# RadarControl_V1_00.net
KiCad netlist of a schematic drawn in Altium Designer
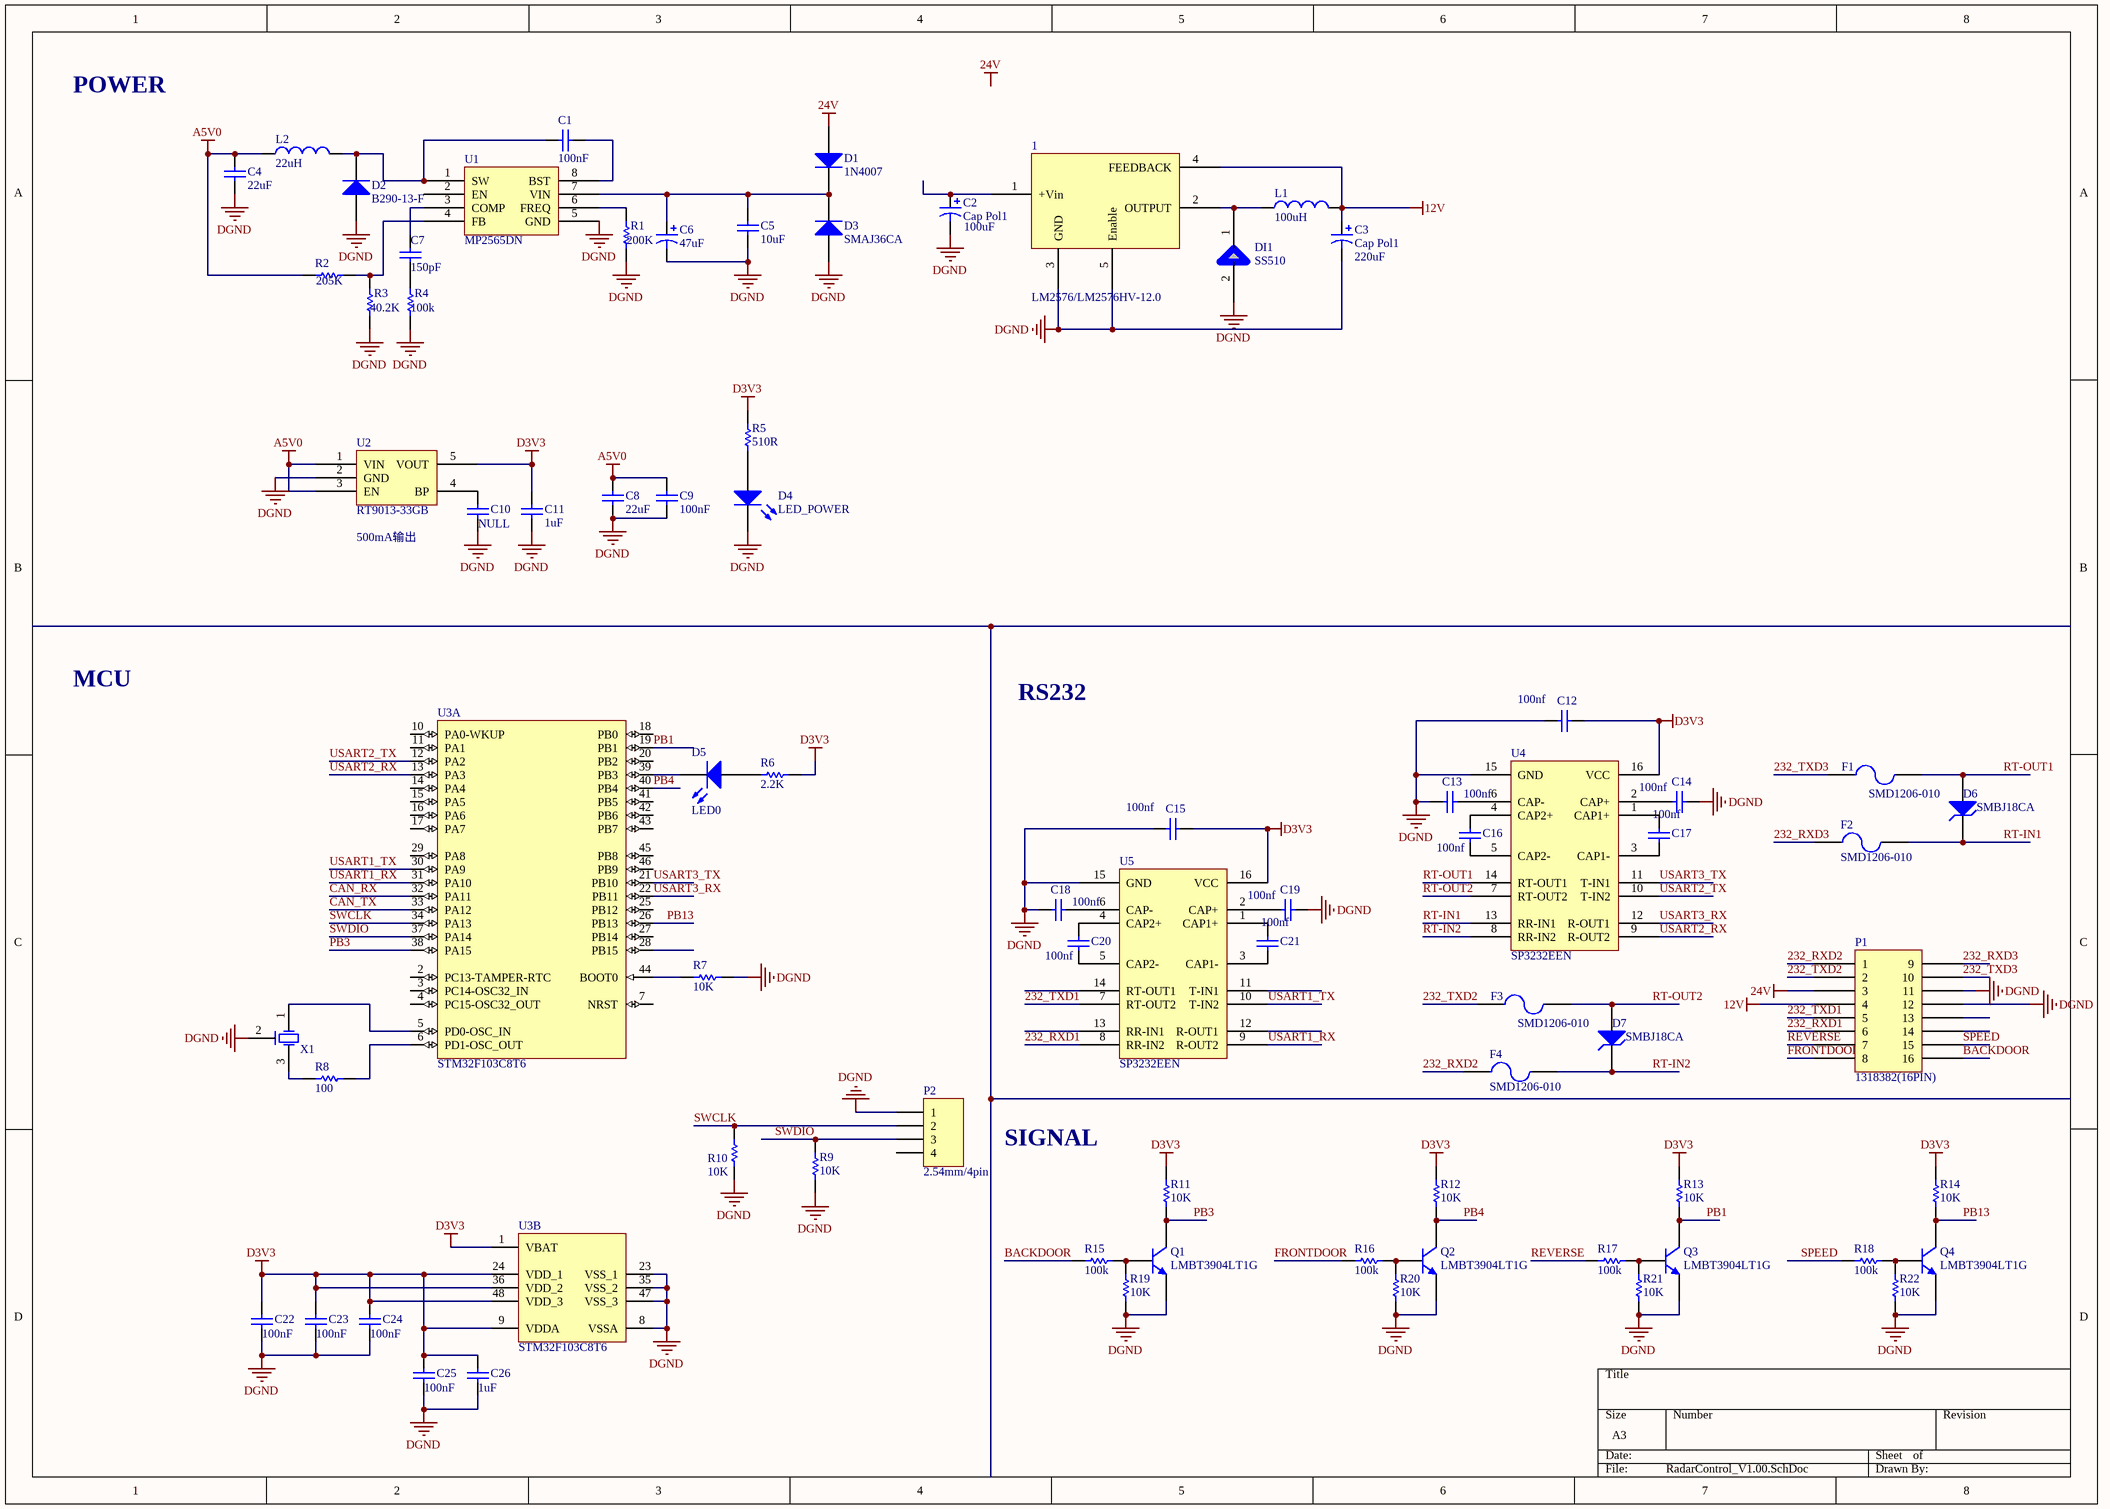
[diagram p0: RadarControl_V1.00.SchDoc]

(export (version "E")
  (design (tool "Eeschema 10.0.6"))
  (components
    (comp (ref "1")
      (value "LM2576/LM2576HV-12.0")
      (footprint "LM25761")
      (libsource (lib "Schlib1") (part "LM2576-FIX"))
    )
    (comp (ref "C1")
      (value "100nF")
      (footprint "0603")
      (description "Capacitor")
      (fields (field (name "PUBLISHER") "Altium Limited"))
      (libsource (lib "Miscellaneous Devices") (part "Cap"))
    )
    (comp (ref "C2")
      (value "Cap Pol1")
      (footprint "Cap-100uF-220uF")
      (description "Polarized Capacitor (Radial)")
      (fields (field (name "ALTIUM_VALUE") "100uF") (field (name "PUBLISHER") "Altium Limited"))
      (libsource (lib "Miscellaneous Devices") (part "Cap Pol1"))
    )
    (comp (ref "C3")
      (value "Cap Pol1")
      (footprint "Cap-100uF-220uF")
      (description "Polarized Capacitor (Radial)")
      (fields (field (name "ALTIUM_VALUE") "220uF") (field (name "PUBLISHER") "Altium Limited"))
      (libsource (lib "Miscellaneous Devices") (part "Cap Pol1"))
    )
    (comp (ref "C4")
      (value "22uF")
      (footprint "0805")
      (description "Capacitor,50V")
      (fields (field (name "PUBLISHER") "Altium Limited"))
      (libsource (lib "Miscellaneous Devices") (part "Cap"))
    )
    (comp (ref "C5")
      (value "10uF")
      (footprint "0805")
      (description "Capacitor,50V")
      (fields (field (name "PUBLISHER") "Altium Limited"))
      (libsource (lib "Miscellaneous Devices") (part "Cap"))
    )
    (comp (ref "C6")
      (value "47uF")
      (footprint "cap_pol_8*10.2")
      (description "Polarized Capacitor (Radial)")
      (fields (field (name "PUBLISHER") "Altium Limited"))
      (libsource (lib "Miscellaneous Devices") (part "Cap Pol1"))
    )
    (comp (ref "C7")
      (value "150pF")
      (footprint "0603")
      (description "Capacitor")
      (fields (field (name "PUBLISHER") "Altium Limited"))
      (libsource (lib "Miscellaneous Devices") (part "Cap"))
    )
    (comp (ref "C8")
      (value "22uF")
      (footprint "1206")
      (description "Capacitor")
      (fields (field (name "PUBLISHER") "Altium Limited"))
      (libsource (lib "Miscellaneous Devices") (part "Cap"))
    )
    (comp (ref "C9")
      (value "100nF")
      (footprint "0402")
      (description "Capacitor 5V")
      (fields (field (name "PUBLISHER") "Altium Limited"))
      (libsource (lib "Miscellaneous Devices") (part "Cap"))
    )
    (comp (ref "C10")
      (value "NULL")
      (footprint "0402")
      (description "Capacitor")
      (fields (field (name "PUBLISHER") "Altium Limited"))
      (libsource (lib "Miscellaneous Devices") (part "Cap"))
    )
    (comp (ref "C11")
      (value "1uF")
      (footprint "0402")
      (description "Capacitor 3V3")
      (fields (field (name "PUBLISHER") "Altium Limited"))
      (libsource (lib "Miscellaneous Devices") (part "Cap"))
    )
    (comp (ref "C12")
      (value "100nf")
      (footprint "0402")
      (description "Capacitor")
      (fields (field (name "PUBLISHER") "Altium Limited"))
      (libsource (lib "Miscellaneous Devices") (part "Cap"))
    )
    (comp (ref "C13")
      (value "100nf")
      (footprint "0402")
      (description "Capacitor")
      (fields (field (name "PUBLISHER") "Altium Limited"))
      (libsource (lib "Miscellaneous Devices") (part "Cap"))
    )
    (comp (ref "C14")
      (value "100nf")
      (footprint "0402")
      (description "Capacitor")
      (fields (field (name "PUBLISHER") "Altium Limited"))
      (libsource (lib "Miscellaneous Devices") (part "Cap"))
    )
    (comp (ref "C15")
      (value "100nf")
      (footprint "0402")
      (description "Capacitor")
      (fields (field (name "PUBLISHER") "Altium Limited"))
      (libsource (lib "Miscellaneous Devices") (part "Cap"))
    )
    (comp (ref "C16")
      (value "100nf")
      (footprint "0402")
      (description "Capacitor")
      (fields (field (name "PUBLISHER") "Altium Limited"))
      (libsource (lib "Miscellaneous Devices") (part "Cap"))
    )
    (comp (ref "C17")
      (value "100nf")
      (footprint "0402")
      (description "Capacitor")
      (fields (field (name "PUBLISHER") "Altium Limited"))
      (libsource (lib "Miscellaneous Devices") (part "Cap"))
    )
    (comp (ref "C18")
      (value "100nf")
      (footprint "0402")
      (description "Capacitor")
      (fields (field (name "PUBLISHER") "Altium Limited"))
      (libsource (lib "Miscellaneous Devices") (part "Cap"))
    )
    (comp (ref "C19")
      (value "100nf")
      (footprint "0402")
      (description "Capacitor")
      (fields (field (name "PUBLISHER") "Altium Limited"))
      (libsource (lib "Miscellaneous Devices") (part "Cap"))
    )
    (comp (ref "C20")
      (value "100nf")
      (footprint "0402")
      (description "Capacitor")
      (fields (field (name "PUBLISHER") "Altium Limited"))
      (libsource (lib "Miscellaneous Devices") (part "Cap"))
    )
    (comp (ref "C21")
      (value "100nf")
      (footprint "0402")
      (description "Capacitor")
      (fields (field (name "PUBLISHER") "Altium Limited"))
      (libsource (lib "Miscellaneous Devices") (part "Cap"))
    )
    (comp (ref "C22")
      (value "100nF")
      (footprint "0603")
      (description "Capacitor")
      (fields (field (name "PUBLISHER") "Altium Limited"))
      (libsource (lib "Miscellaneous Devices") (part "Cap"))
    )
    (comp (ref "C23")
      (value "100nF")
      (footprint "0402")
      (description "Capacitor")
      (fields (field (name "PUBLISHER") "Altium Limited"))
      (libsource (lib "Miscellaneous Devices") (part "Cap"))
    )
    (comp (ref "C24")
      (value "100nF")
      (footprint "0402")
      (description "Capacitor")
      (fields (field (name "PUBLISHER") "Altium Limited"))
      (libsource (lib "Miscellaneous Devices") (part "Cap"))
    )
    (comp (ref "C25")
      (value "100nF")
      (footprint "0402")
      (description "Capacitor")
      (fields (field (name "PUBLISHER") "Altium Limited"))
      (libsource (lib "Miscellaneous Devices") (part "Cap"))
    )
    (comp (ref "C26")
      (value "1uF")
      (footprint "0402")
      (description "Capacitor")
      (fields (field (name "PUBLISHER") "Altium Limited"))
      (libsource (lib "Miscellaneous Devices") (part "Cap"))
    )
    (comp (ref "D1")
      (value "1N4007")
      (footprint "B290")
      (description "1 Amp General Purpose Rectifier")
      (fields (field (name "PUBLISHER") "Altium Limited"))
      (libsource (lib "Miscellaneous Devices") (part "Diode 1N4007"))
    )
    (comp (ref "D2")
      (value "B290-13-F")
      (footprint "B290")
      (description "Default Diode")
      (fields (field (name "PUBLISHER") "Altium Limited"))
      (libsource (lib "Miscellaneous Devices") (part "Diode"))
    )
    (comp (ref "D3")
      (value "SMAJ36CA")
      (footprint "B290")
      (description "1 Amp General Purpose Rectifier")
      (fields (field (name "PUBLISHER") "Altium Limited"))
      (libsource (lib "Miscellaneous Devices") (part "Diode 1N4007"))
    )
    (comp (ref "D4")
      (value "LED_POWER")
      (footprint "0805-LED")
      (description "Typical INFRARED GaAs LED")
      (fields (field (name "PUBLISHER") "Altium Limited"))
      (libsource (lib "Miscellaneous Devices") (part "LED0"))
    )
    (comp (ref "D5")
      (value "LED0")
      (footprint "0805-LED")
      (description "green LED")
      (fields (field (name "PUBLISHER") "Altium Limited"))
      (libsource (lib "Miscellaneous Devices") (part "LED0"))
    )
    (comp (ref "D6")
      (value "SMBJ18CA")
      (footprint "SMB")
      (description "Zener Diode")
      (fields (field (name "PUBLISHER") "Altium Limited"))
      (libsource (lib "Miscellaneous Devices") (part "D Zener"))
    )
    (comp (ref "D7")
      (value "SMBJ18CA")
      (footprint "SMB")
      (description "Zener Diode")
      (fields (field (name "PUBLISHER") "Altium Limited"))
      (libsource (lib "Miscellaneous Devices") (part "D Zener"))
    )
    (comp (ref "DI1") (value "SS510") (footprint "SS510") (libsource (lib "Schlib2") (part "SS510")))
    (comp (ref "F1")
      (value "SMD1206-010")
      (footprint "1206")
      (description "Fuse")
      (fields (field (name "PUBLISHER") "Altium Limited"))
      (libsource (lib "Miscellaneous Devices") (part "Fuse 2"))
    )
    (comp (ref "F2")
      (value "SMD1206-010")
      (footprint "1206")
      (description "Fuse")
      (fields (field (name "PUBLISHER") "Altium Limited"))
      (libsource (lib "Miscellaneous Devices") (part "Fuse 2"))
    )
    (comp (ref "F3")
      (value "SMD1206-010")
      (footprint "1206")
      (description "Fuse")
      (fields (field (name "PUBLISHER") "Altium Limited"))
      (libsource (lib "Miscellaneous Devices") (part "Fuse 2"))
    )
    (comp (ref "F4")
      (value "SMD1206-010")
      (footprint "1206")
      (description "Fuse")
      (fields (field (name "PUBLISHER") "Altium Limited"))
      (libsource (lib "Miscellaneous Devices") (part "Fuse 2"))
    )
    (comp (ref "L1")
      (value "100uH")
      (footprint "GDRH104R-1R0MT")
      (description "Inductor")
      (fields (field (name "PUBLISHER") "Altium Limited"))
      (libsource (lib "原理图库") (part "Inductor"))
    )
    (comp (ref "L2")
      (value "22uH")
      (footprint "10*10Inductor")
      (description "Inductor, 1A")
      (fields (field (name "PUBLISHER") "Altium Limited"))
      (libsource (lib "Miscellaneous Devices") (part "Inductor"))
    )
    (comp (ref "P1")
      (value "1318382(16PIN)")
      (footprint "16pin 1318382")
      (libsource (lib "16PIN") (part "16PIN"))
    )
    (comp (ref "P2")
      (value "2.54mm/4pin")
      (footprint "HDR1X4")
      (description "Header, 4-Pin")
      (fields (field (name "PUBLISHER") "Altium Limited"))
      (libsource (lib "Miscellaneous Connectors") (part "Header 4"))
    )
    (comp (ref "Q1")
      (value "LMBT3904LT1G")
      (footprint "LC-SOT-23(SOT-23-3)")
      (description "NPN General Purpose Amplifier")
      (fields (field (name "PUBLISHER") "Altium Limited"))
      (libsource (lib "Miscellaneous Devices") (part "2N3904"))
    )
    (comp (ref "Q2")
      (value "LMBT3904LT1G")
      (footprint "LC-SOT-23(SOT-23-3)")
      (description "NPN General Purpose Amplifier")
      (fields (field (name "PUBLISHER") "Altium Limited"))
      (libsource (lib "Miscellaneous Devices") (part "2N3904"))
    )
    (comp (ref "Q3")
      (value "LMBT3904LT1G")
      (footprint "LC-SOT-23(SOT-23-3)")
      (description "NPN General Purpose Amplifier")
      (fields (field (name "PUBLISHER") "Altium Limited"))
      (libsource (lib "Miscellaneous Devices") (part "2N3904"))
    )
    (comp (ref "Q4")
      (value "LMBT3904LT1G")
      (footprint "LC-SOT-23(SOT-23-3)")
      (description "NPN General Purpose Amplifier")
      (fields (field (name "PUBLISHER") "Altium Limited"))
      (libsource (lib "Miscellaneous Devices") (part "2N3904"))
    )
    (comp (ref "R1")
      (value "200K")
      (footprint "0402")
      (description "Resistor")
      (fields (field (name "PUBLISHER") "Altium Limited"))
      (libsource (lib "Miscellaneous Devices") (part "Res1"))
    )
    (comp (ref "R2")
      (value "205K")
      (footprint "0603")
      (description "Resistor")
      (fields (field (name "PUBLISHER") "Altium Limited"))
      (libsource (lib "Miscellaneous Devices") (part "Res1"))
    )
    (comp (ref "R3")
      (value "40.2K")
      (footprint "0603")
      (description "Resistor")
      (fields (field (name "PUBLISHER") "Altium Limited"))
      (libsource (lib "Miscellaneous Devices") (part "Res1"))
    )
    (comp (ref "R4")
      (value "100k")
      (footprint "0603")
      (description "Resistor")
      (fields (field (name "PUBLISHER") "Altium Limited"))
      (libsource (lib "Miscellaneous Devices") (part "Res1"))
    )
    (comp (ref "R5")
      (value "510R")
      (footprint "0603")
      (description "Resistor")
      (fields (field (name "PUBLISHER") "Altium Limited"))
      (libsource (lib "Miscellaneous Devices") (part "Res1"))
    )
    (comp (ref "R6")
      (value "2.2K")
      (footprint "0402")
      (description "Resistor")
      (fields (field (name "PUBLISHER") "Altium Limited"))
      (libsource (lib "Miscellaneous Devices") (part "Res1"))
    )
    (comp (ref "R7")
      (value "10K")
      (footprint "0402")
      (description "Resistor")
      (fields (field (name "PUBLISHER") "Altium Limited"))
      (libsource (lib "Miscellaneous Devices") (part "Res1"))
    )
    (comp (ref "R8")
      (value "100")
      (footprint "0603")
      (description "Resistor")
      (fields (field (name "PUBLISHER") "Altium Limited"))
      (libsource (lib "Miscellaneous Devices") (part "Res1"))
    )
    (comp (ref "R9")
      (value "10K")
      (footprint "0402")
      (description "Resistor")
      (fields (field (name "Comment") "1K") (field (name "PUBLISHER") "Altium Limited"))
      (libsource (lib "Miscellaneous Devices") (part "Res1"))
    )
    (comp (ref "R10")
      (value "10K")
      (footprint "0402")
      (description "Resistor")
      (fields (field (name "Comment") "1K") (field (name "PUBLISHER") "Altium Limited"))
      (libsource (lib "Miscellaneous Devices") (part "Res1"))
    )
    (comp (ref "R11")
      (value "10K")
      (footprint "0402")
      (description "Resistor")
      (fields (field (name "PUBLISHER") "Altium Limited"))
      (libsource (lib "Miscellaneous Devices") (part "Res1"))
    )
    (comp (ref "R12")
      (value "10K")
      (footprint "0402")
      (description "Resistor")
      (fields (field (name "PUBLISHER") "Altium Limited"))
      (libsource (lib "Miscellaneous Devices") (part "Res1"))
    )
    (comp (ref "R13")
      (value "10K")
      (footprint "0402")
      (description "Resistor")
      (fields (field (name "PUBLISHER") "Altium Limited"))
      (libsource (lib "Miscellaneous Devices") (part "Res1"))
    )
    (comp (ref "R14")
      (value "10K")
      (footprint "0402")
      (description "Resistor")
      (fields (field (name "PUBLISHER") "Altium Limited"))
      (libsource (lib "Miscellaneous Devices") (part "Res1"))
    )
    (comp (ref "R15")
      (value "100k")
      (footprint "0402")
      (description "Resistor")
      (fields (field (name "PUBLISHER") "Altium Limited"))
      (libsource (lib "Miscellaneous Devices") (part "Res1"))
    )
    (comp (ref "R16")
      (value "100k")
      (footprint "0402")
      (description "Resistor")
      (fields (field (name "PUBLISHER") "Altium Limited"))
      (libsource (lib "Miscellaneous Devices") (part "Res1"))
    )
    (comp (ref "R17")
      (value "100k")
      (footprint "0402")
      (description "Resistor")
      (fields (field (name "PUBLISHER") "Altium Limited"))
      (libsource (lib "Miscellaneous Devices") (part "Res1"))
    )
    (comp (ref "R18")
      (value "100k")
      (footprint "0402")
      (description "Resistor")
      (fields (field (name "PUBLISHER") "Altium Limited"))
      (libsource (lib "Miscellaneous Devices") (part "Res1"))
    )
    (comp (ref "R19")
      (value "10K")
      (footprint "0402")
      (description "Resistor")
      (fields (field (name "PUBLISHER") "Altium Limited"))
      (libsource (lib "Miscellaneous Devices") (part "Res1"))
    )
    (comp (ref "R20")
      (value "10K")
      (footprint "0402")
      (description "Resistor")
      (fields (field (name "PUBLISHER") "Altium Limited"))
      (libsource (lib "Miscellaneous Devices") (part "Res1"))
    )
    (comp (ref "R21")
      (value "10K")
      (footprint "0402")
      (description "Resistor")
      (fields (field (name "PUBLISHER") "Altium Limited"))
      (libsource (lib "Miscellaneous Devices") (part "Res1"))
    )
    (comp (ref "R22")
      (value "10K")
      (footprint "0402")
      (description "Resistor")
      (fields (field (name "PUBLISHER") "Altium Limited"))
      (libsource (lib "Miscellaneous Devices") (part "Res1"))
    )
    (comp (ref "U1")
      (value "MP2565DN")
      (footprint "so-8")
      (description "DCDC 4.5V~28V input 1.8V ~5V output low power")
      (libsource (lib "BinFeng_IC") (part "MP1584"))
    )
    (comp (ref "U2")
      (value "RT9013-33GB")
      (footprint "SOT-23-5")
      (libsource (lib "BinFeng_IC") (part "RT9193"))
    )
    (comp (ref "U3")
      (value "STM32F103C8T6")
      (footprint "STM-LQFP48_M")
      (libsource (lib "STMicroelectronics STM32 F1") (part "STM32F103C8T6"))
    )
    (comp (ref "U4") (value "SP3232EEN") (footprint "SO-16") (libsource (lib "changyong") (part "MAX202")))
    (comp (ref "U5") (value "SP3232EEN") (footprint "SO-16") (libsource (lib "changyong") (part "MAX202")))
    (comp (ref "X1") (value "8M smd") (footprint "8M") (libsource (lib "Schlib1") (part "8M smd")))
  )
  (nets
    (net (code "1") (name "/232_RXD1") (class "Default")
      (node (ref "P1") (pin "6") (pinfunction "6_6") (pintype "passive"))
      (node (ref "U5") (pin "8") (pinfunction "RR-IN2_8") (pintype "passive"))
    )
    (net (code "2") (name "/232_RXD2") (class "Default")
      (node (ref "F4") (pin "1") (pinfunction "1_1") (pintype "passive"))
      (node (ref "P1") (pin "1") (pinfunction "1_1") (pintype "passive"))
    )
    (net (code "3") (name "/232_RXD3") (class "Default")
      (node (ref "F2") (pin "1") (pinfunction "1_1") (pintype "passive"))
      (node (ref "P1") (pin "9") (pinfunction "9_9") (pintype "passive"))
    )
    (net (code "4") (name "/232_TXD1") (class "Default")
      (node (ref "P1") (pin "5") (pinfunction "5_5") (pintype "passive"))
      (node (ref "U5") (pin "7") (pinfunction "RT-OUT2_7") (pintype "passive"))
    )
    (net (code "5") (name "/232_TXD2") (class "Default")
      (node (ref "F3") (pin "1") (pinfunction "1_1") (pintype "passive"))
      (node (ref "P1") (pin "2") (pinfunction "2_2") (pintype "passive"))
    )
    (net (code "6") (name "/232_TXD3") (class "Default")
      (node (ref "F1") (pin "1") (pinfunction "1_1") (pintype "passive"))
      (node (ref "P1") (pin "10") (pinfunction "10_10") (pintype "passive"))
    )
    (net (code "7") (name "/BACKDOOR") (class "Default")
      (node (ref "P1") (pin "16") (pinfunction "16_16") (pintype "passive"))
      (node (ref "R15") (pin "2") (pinfunction "2_2") (pintype "passive"))
    )
    (net (code "8") (name "/CAN_RX") (class "Default")
      (node (ref "U3") (pin "32") (pinfunction "PA11_32") (pintype "bidirectional"))
    )
    (net (code "9") (name "/CAN_TX") (class "Default")
      (node (ref "U3") (pin "33") (pinfunction "PA12_33") (pintype "bidirectional"))
    )
    (net (code "10") (name "/FRONTDOOR") (class "Default")
      (node (ref "P1") (pin "8") (pinfunction "8_8") (pintype "passive"))
      (node (ref "R16") (pin "2") (pinfunction "2_2") (pintype "passive"))
    )
    (net (code "11") (name "/PB1") (class "Default")
      (node (ref "Q3") (pin "3") (pinfunction "C_3") (pintype "passive"))
      (node (ref "R13") (pin "1") (pinfunction "1_1") (pintype "passive"))
      (node (ref "U3") (pin "19") (pinfunction "PB1_19") (pintype "bidirectional"))
    )
    (net (code "12") (name "/PB3") (class "Default")
      (node (ref "Q1") (pin "3") (pinfunction "C_3") (pintype "passive"))
      (node (ref "R11") (pin "1") (pinfunction "1_1") (pintype "passive"))
      (node (ref "U3") (pin "38") (pinfunction "PA15_38") (pintype "bidirectional"))
    )
    (net (code "13") (name "/PB4") (class "Default")
      (node (ref "Q2") (pin "3") (pinfunction "C_3") (pintype "passive"))
      (node (ref "R12") (pin "1") (pinfunction "1_1") (pintype "passive"))
      (node (ref "U3") (pin "40") (pinfunction "PB4_40") (pintype "bidirectional"))
    )
    (net (code "14") (name "/PB13") (class "Default")
      (node (ref "Q4") (pin "3") (pinfunction "C_3") (pintype "passive"))
      (node (ref "R14") (pin "1") (pinfunction "1_1") (pintype "passive"))
      (node (ref "U3") (pin "26") (pinfunction "PB13_26") (pintype "bidirectional"))
    )
    (net (code "15") (name "/REVERSE") (class "Default")
      (node (ref "P1") (pin "7") (pinfunction "7_7") (pintype "passive"))
      (node (ref "R17") (pin "2") (pinfunction "2_2") (pintype "passive"))
    )
    (net (code "16") (name "/RT-IN1") (class "Default")
      (node (ref "D6") (pin "2") (pinfunction "K_2") (pintype "passive"))
      (node (ref "F2") (pin "2") (pinfunction "2_2") (pintype "passive"))
      (node (ref "U4") (pin "13") (pinfunction "RR-IN1_13") (pintype "passive"))
    )
    (net (code "17") (name "/RT-IN2") (class "Default")
      (node (ref "D7") (pin "2") (pinfunction "K_2") (pintype "passive"))
      (node (ref "F4") (pin "2") (pinfunction "2_2") (pintype "passive"))
      (node (ref "U4") (pin "8") (pinfunction "RR-IN2_8") (pintype "passive"))
    )
    (net (code "18") (name "/RT-OUT1") (class "Default")
      (node (ref "D6") (pin "1") (pinfunction "A_1") (pintype "passive"))
      (node (ref "F1") (pin "2") (pinfunction "2_2") (pintype "passive"))
      (node (ref "U4") (pin "14") (pinfunction "RT-OUT1_14") (pintype "passive"))
    )
    (net (code "19") (name "/RT-OUT2") (class "Default")
      (node (ref "D7") (pin "1") (pinfunction "A_1") (pintype "passive"))
      (node (ref "F3") (pin "2") (pinfunction "2_2") (pintype "passive"))
      (node (ref "U4") (pin "7") (pinfunction "RT-OUT2_7") (pintype "passive"))
    )
    (net (code "20") (name "/SPEED") (class "Default")
      (node (ref "P1") (pin "15") (pinfunction "15_15") (pintype "passive"))
      (node (ref "R18") (pin "2") (pinfunction "2_2") (pintype "passive"))
    )
    (net (code "21") (name "/SWCLK") (class "Default")
      (node (ref "P2") (pin "2") (pinfunction "2_2") (pintype "passive"))
      (node (ref "R10") (pin "1") (pinfunction "1_1") (pintype "passive"))
      (node (ref "U3") (pin "34") (pinfunction "PA13_34") (pintype "bidirectional"))
    )
    (net (code "22") (name "/SWDIO") (class "Default")
      (node (ref "P2") (pin "3") (pinfunction "3_3") (pintype "passive"))
      (node (ref "R9") (pin "1") (pinfunction "1_1") (pintype "passive"))
      (node (ref "U3") (pin "37") (pinfunction "PA14_37") (pintype "bidirectional"))
    )
    (net (code "23") (name "/USART1_RX") (class "Default")
      (node (ref "U3") (pin "31") (pinfunction "PA10_31") (pintype "bidirectional"))
      (node (ref "U5") (pin "9") (pinfunction "R-OUT2_9") (pintype "passive"))
    )
    (net (code "24") (name "/USART1_TX") (class "Default")
      (node (ref "U3") (pin "30") (pinfunction "PA9_30") (pintype "bidirectional"))
      (node (ref "U5") (pin "10") (pinfunction "T-IN2_10") (pintype "passive"))
    )
    (net (code "25") (name "/USART2_RX") (class "Default")
      (node (ref "U3") (pin "13") (pinfunction "PA3_13") (pintype "bidirectional"))
      (node (ref "U4") (pin "9") (pinfunction "R-OUT2_9") (pintype "passive"))
    )
    (net (code "26") (name "/USART2_TX") (class "Default")
      (node (ref "U3") (pin "12") (pinfunction "PA2_12") (pintype "bidirectional"))
      (node (ref "U4") (pin "10") (pinfunction "T-IN2_10") (pintype "passive"))
    )
    (net (code "27") (name "/USART3_RX") (class "Default")
      (node (ref "U3") (pin "22") (pinfunction "PB11_22") (pintype "bidirectional"))
      (node (ref "U4") (pin "12") (pinfunction "R-OUT1_12") (pintype "passive"))
    )
    (net (code "28") (name "/USART3_TX") (class "Default")
      (node (ref "U3") (pin "21") (pinfunction "PB10_21") (pintype "bidirectional"))
      (node (ref "U4") (pin "11") (pinfunction "T-IN1_11") (pintype "passive"))
    )
    (net (code "29") (name "12V") (class "Default")
      (node (ref "1") (pin "4") (pinfunction "FEEDBACK_4") (pintype "passive"))
      (node (ref "C3") (pin "1") (pinfunction "1_1") (pintype "passive"))
      (node (ref "L1") (pin "2") (pinfunction "2_2") (pintype "passive"))
      (node (ref "P1") (pin "4") (pinfunction "4_4") (pintype "passive"))
    )
    (net (code "30") (name "24V") (class "Default")
      (node (ref "D1") (pin "1") (pinfunction "A_1") (pintype "passive"))
      (node (ref "P1") (pin "3") (pinfunction "3_3") (pintype "passive"))
    )
    (net (code "31") (name "A5V0") (class "Default")
      (node (ref "C4") (pin "2") (pinfunction "2_2") (pintype "passive"))
      (node (ref "C8") (pin "1") (pinfunction "1_1") (pintype "passive"))
      (node (ref "C9") (pin "2") (pinfunction "2_2") (pintype "passive"))
      (node (ref "L2") (pin "1") (pinfunction "1_1") (pintype "passive"))
      (node (ref "R2") (pin "2") (pinfunction "2_2") (pintype "passive"))
      (node (ref "U2") (pin "1") (pinfunction "VIN_1") (pintype "passive"))
      (node (ref "U2") (pin "3") (pinfunction "EN_3") (pintype "passive"))
    )
    (net (code "32") (name "D3V3") (class "Default")
      (node (ref "C11") (pin "2") (pinfunction "2_2") (pintype "passive"))
      (node (ref "C12") (pin "2") (pinfunction "2_2") (pintype "passive"))
      (node (ref "C15") (pin "2") (pinfunction "2_2") (pintype "passive"))
      (node (ref "C22") (pin "2") (pinfunction "2_2") (pintype "passive"))
      (node (ref "C23") (pin "2") (pinfunction "2_2") (pintype "passive"))
      (node (ref "C24") (pin "2") (pinfunction "2_2") (pintype "passive"))
      (node (ref "C25") (pin "2") (pinfunction "2_2") (pintype "passive"))
      (node (ref "C26") (pin "2") (pinfunction "2_2") (pintype "passive"))
      (node (ref "R11") (pin "2") (pinfunction "2_2") (pintype "passive"))
      (node (ref "R12") (pin "2") (pinfunction "2_2") (pintype "passive"))
      (node (ref "R13") (pin "2") (pinfunction "2_2") (pintype "passive"))
      (node (ref "R14") (pin "2") (pinfunction "2_2") (pintype "passive"))
      (node (ref "R5") (pin "2") (pinfunction "2_2") (pintype "passive"))
      (node (ref "R6") (pin "2") (pinfunction "2_2") (pintype "passive"))
      (node (ref "U2") (pin "5") (pinfunction "VOUT_5") (pintype "passive"))
      (node (ref "U3") (pin "1") (pinfunction "VBAT_1") (pintype "power_in"))
      (node (ref "U3") (pin "24") (pinfunction "VDD_1_24") (pintype "power_in"))
      (node (ref "U3") (pin "36") (pinfunction "VDD_2_36") (pintype "power_in"))
      (node (ref "U3") (pin "48") (pinfunction "VDD_3_48") (pintype "power_in"))
      (node (ref "U3") (pin "9") (pinfunction "VDDA_9") (pintype "power_in"))
      (node (ref "U4") (pin "16") (pinfunction "VCC_16") (pintype "passive"))
      (node (ref "U5") (pin "16") (pinfunction "VCC_16") (pintype "passive"))
    )
    (net (code "33") (name "DGND") (class "Default")
      (node (ref "1") (pin "3") (pinfunction "GND_3") (pintype "passive"))
      (node (ref "1") (pin "5") (pinfunction "Enable_5") (pintype "passive"))
      (node (ref "C10") (pin "1") (pinfunction "1_1") (pintype "passive"))
      (node (ref "C11") (pin "1") (pinfunction "1_1") (pintype "passive"))
      (node (ref "C12") (pin "1") (pinfunction "1_1") (pintype "passive"))
      (node (ref "C13") (pin "1") (pinfunction "1_1") (pintype "passive"))
      (node (ref "C14") (pin "1") (pinfunction "1_1") (pintype "passive"))
      (node (ref "C15") (pin "1") (pinfunction "1_1") (pintype "passive"))
      (node (ref "C18") (pin "1") (pinfunction "1_1") (pintype "passive"))
      (node (ref "C19") (pin "1") (pinfunction "1_1") (pintype "passive"))
      (node (ref "C2") (pin "2") (pinfunction "2_2") (pintype "passive"))
      (node (ref "C22") (pin "1") (pinfunction "1_1") (pintype "passive"))
      (node (ref "C23") (pin "1") (pinfunction "1_1") (pintype "passive"))
      (node (ref "C24") (pin "1") (pinfunction "1_1") (pintype "passive"))
      (node (ref "C25") (pin "1") (pinfunction "1_1") (pintype "passive"))
      (node (ref "C26") (pin "1") (pinfunction "1_1") (pintype "passive"))
      (node (ref "C3") (pin "2") (pinfunction "2_2") (pintype "passive"))
      (node (ref "C4") (pin "1") (pinfunction "1_1") (pintype "passive"))
      (node (ref "C5") (pin "1") (pinfunction "1_1") (pintype "passive"))
      (node (ref "C6") (pin "2") (pinfunction "2_2") (pintype "passive"))
      (node (ref "C8") (pin "2") (pinfunction "2_2") (pintype "passive"))
      (node (ref "C9") (pin "1") (pinfunction "1_1") (pintype "passive"))
      (node (ref "D2") (pin "1") (pinfunction "A_1") (pintype "passive"))
      (node (ref "D3") (pin "1") (pinfunction "A_1") (pintype "passive"))
      (node (ref "D4") (pin "2") (pinfunction "K_2") (pintype "passive"))
      (node (ref "DI1") (pin "2") (pinfunction "OUT_2") (pintype "passive"))
      (node (ref "P1") (pin "11") (pinfunction "11_11") (pintype "passive"))
      (node (ref "P1") (pin "12") (pinfunction "12_12") (pintype "passive"))
      (node (ref "P2") (pin "1") (pinfunction "1_1") (pintype "passive"))
      (node (ref "Q1") (pin "1") (pinfunction "E_1") (pintype "passive"))
      (node (ref "Q2") (pin "1") (pinfunction "E_1") (pintype "passive"))
      (node (ref "Q3") (pin "1") (pinfunction "E_1") (pintype "passive"))
      (node (ref "Q4") (pin "1") (pinfunction "E_1") (pintype "passive"))
      (node (ref "R1") (pin "1") (pinfunction "1_1") (pintype "passive"))
      (node (ref "R10") (pin "2") (pinfunction "2_2") (pintype "passive"))
      (node (ref "R19") (pin "1") (pinfunction "1_1") (pintype "passive"))
      (node (ref "R20") (pin "1") (pinfunction "1_1") (pintype "passive"))
      (node (ref "R21") (pin "1") (pinfunction "1_1") (pintype "passive"))
      (node (ref "R22") (pin "1") (pinfunction "1_1") (pintype "passive"))
      (node (ref "R3") (pin "1") (pinfunction "1_1") (pintype "passive"))
      (node (ref "R4") (pin "1") (pinfunction "1_1") (pintype "passive"))
      (node (ref "R7") (pin "2") (pinfunction "2_2") (pintype "passive"))
      (node (ref "R9") (pin "2") (pinfunction "2_2") (pintype "passive"))
      (node (ref "U1") (pin "5") (pinfunction "GND_5") (pintype "passive"))
      (node (ref "U2") (pin "2") (pinfunction "GND_2") (pintype "passive"))
      (node (ref "U3") (pin "23") (pinfunction "VSS_1_23") (pintype "power_in"))
      (node (ref "U3") (pin "35") (pinfunction "VSS_2_35") (pintype "power_in"))
      (node (ref "U3") (pin "47") (pinfunction "VSS_3_47") (pintype "power_in"))
      (node (ref "U3") (pin "8") (pinfunction "VSSA_8") (pintype "power_in"))
      (node (ref "U4") (pin "15") (pinfunction "GND_15") (pintype "passive"))
      (node (ref "U5") (pin "15") (pinfunction "GND_15") (pintype "passive"))
      (node (ref "X1") (pin "2") (pinfunction "GND_2") (pintype "passive"))
    )
    (net (code "34") (name "Net-(1-+Vin)") (class "Default")
      (node (ref "1") (pin "1") (pinfunction "+Vin_1") (pintype "passive"))
      (node (ref "C2") (pin "1") (pinfunction "1_1") (pintype "passive"))
    )
    (net (code "35") (name "Net-(1-OUTPUT)") (class "Default")
      (node (ref "1") (pin "2") (pinfunction "OUTPUT_2") (pintype "passive"))
      (node (ref "DI1") (pin "1") (pinfunction "OUT_1") (pintype "passive"))
      (node (ref "L1") (pin "1") (pinfunction "1_1") (pintype "passive"))
    )
    (net (code "36") (name "Net-(C7-Pad2)") (class "Default")
      (node (ref "C7") (pin "2") (pinfunction "2_2") (pintype "passive"))
      (node (ref "R4") (pin "2") (pinfunction "2_2") (pintype "passive"))
    )
    (net (code "37") (name "Net-(D1-K)") (class "Default")
      (node (ref "C5") (pin "2") (pinfunction "2_2") (pintype "passive"))
      (node (ref "C6") (pin "1") (pinfunction "1_1") (pintype "passive"))
      (node (ref "D1") (pin "2") (pinfunction "K_2") (pintype "passive"))
      (node (ref "D3") (pin "2") (pinfunction "K_2") (pintype "passive"))
      (node (ref "U1") (pin "7") (pinfunction "VIN_7") (pintype "passive"))
    )
    (net (code "38") (name "Net-(D2-K)") (class "Default")
      (node (ref "C1") (pin "2") (pinfunction "2_2") (pintype "passive"))
      (node (ref "D2") (pin "2") (pinfunction "K_2") (pintype "passive"))
      (node (ref "L2") (pin "2") (pinfunction "2_2") (pintype "passive"))
      (node (ref "U1") (pin "1") (pinfunction "SW_1") (pintype "passive"))
    )
    (net (code "39") (name "Net-(D4-A)") (class "Default")
      (node (ref "D4") (pin "1") (pinfunction "A_1") (pintype "passive"))
      (node (ref "R5") (pin "1") (pinfunction "1_1") (pintype "passive"))
    )
    (net (code "40") (name "Net-(D5-A)") (class "Default")
      (node (ref "D5") (pin "1") (pinfunction "A_1") (pintype "passive"))
      (node (ref "R6") (pin "1") (pinfunction "1_1") (pintype "passive"))
    )
    (net (code "41") (name "Net-(D5-K)") (class "Default")
      (node (ref "D5") (pin "2") (pinfunction "K_2") (pintype "passive"))
      (node (ref "U3") (pin "39") (pinfunction "PB3_39") (pintype "bidirectional"))
    )
    (net (code "42") (name "Net-(Q1-B)") (class "Default")
      (node (ref "Q1") (pin "2") (pinfunction "B_2") (pintype "passive"))
      (node (ref "R15") (pin "1") (pinfunction "1_1") (pintype "passive"))
      (node (ref "R19") (pin "2") (pinfunction "2_2") (pintype "passive"))
    )
    (net (code "43") (name "Net-(Q2-B)") (class "Default")
      (node (ref "Q2") (pin "2") (pinfunction "B_2") (pintype "passive"))
      (node (ref "R16") (pin "1") (pinfunction "1_1") (pintype "passive"))
      (node (ref "R20") (pin "2") (pinfunction "2_2") (pintype "passive"))
    )
    (net (code "44") (name "Net-(Q3-B)") (class "Default")
      (node (ref "Q3") (pin "2") (pinfunction "B_2") (pintype "passive"))
      (node (ref "R17") (pin "1") (pinfunction "1_1") (pintype "passive"))
      (node (ref "R21") (pin "2") (pinfunction "2_2") (pintype "passive"))
    )
    (net (code "45") (name "Net-(Q4-B)") (class "Default")
      (node (ref "Q4") (pin "2") (pinfunction "B_2") (pintype "passive"))
      (node (ref "R18") (pin "1") (pinfunction "1_1") (pintype "passive"))
      (node (ref "R22") (pin "2") (pinfunction "2_2") (pintype "passive"))
    )
    (net (code "46") (name "Net-(U1-BST)") (class "Default")
      (node (ref "C1") (pin "1") (pinfunction "1_1") (pintype "passive"))
      (node (ref "U1") (pin "8") (pinfunction "BST_8") (pintype "passive"))
    )
    (net (code "47") (name "Net-(U1-COMP)") (class "Default")
      (node (ref "C7") (pin "1") (pinfunction "1_1") (pintype "passive"))
      (node (ref "U1") (pin "3") (pinfunction "COMP_3") (pintype "passive"))
    )
    (net (code "48") (name "Net-(U1-FB)") (class "Default")
      (node (ref "R2") (pin "1") (pinfunction "1_1") (pintype "passive"))
      (node (ref "R3") (pin "2") (pinfunction "2_2") (pintype "passive"))
      (node (ref "U1") (pin "4") (pinfunction "FB_4") (pintype "passive"))
    )
    (net (code "49") (name "Net-(U1-FREQ)") (class "Default")
      (node (ref "R1") (pin "2") (pinfunction "2_2") (pintype "passive"))
      (node (ref "U1") (pin "6") (pinfunction "FREQ_6") (pintype "passive"))
    )
    (net (code "50") (name "Net-(U2-BP)") (class "Default")
      (node (ref "C10") (pin "2") (pinfunction "2_2") (pintype "passive"))
      (node (ref "U2") (pin "4") (pinfunction "BP_4") (pintype "passive"))
    )
    (net (code "51") (name "Net-(U3A-BOOT0)") (class "Default")
      (node (ref "R7") (pin "1") (pinfunction "1_1") (pintype "passive"))
      (node (ref "U3") (pin "44") (pinfunction "BOOT0_44") (pintype "input"))
    )
    (net (code "52") (name "Net-(U3A-PD0-OSC_IN)") (class "Default")
      (node (ref "U3") (pin "5") (pinfunction "PD0-OSC_IN_5") (pintype "bidirectional"))
      (node (ref "X1") (pin "1") (pinfunction "OSC1_1") (pintype "passive"))
    )
    (net (code "53") (name "Net-(U3A-PD1-OSC_OUT)") (class "Default")
      (node (ref "R8") (pin "2") (pinfunction "2_2") (pintype "passive"))
      (node (ref "U3") (pin "6") (pinfunction "PD1-OSC_OUT_6") (pintype "bidirectional"))
    )
    (net (code "54") (name "Net-(U4-CAP+)") (class "Default")
      (node (ref "C14") (pin "2") (pinfunction "2_2") (pintype "passive"))
      (node (ref "U4") (pin "2") (pinfunction "CAP+_2") (pintype "passive"))
    )
    (net (code "55") (name "Net-(U4-CAP-)") (class "Default")
      (node (ref "C13") (pin "2") (pinfunction "2_2") (pintype "passive"))
      (node (ref "U4") (pin "6") (pinfunction "CAP-_6") (pintype "passive"))
    )
    (net (code "56") (name "Net-(U4-CAP1+)") (class "Default")
      (node (ref "C17") (pin "2") (pinfunction "2_2") (pintype "passive"))
      (node (ref "U4") (pin "1") (pinfunction "CAP1+_1") (pintype "passive"))
    )
    (net (code "57") (name "Net-(U4-CAP1-)") (class "Default")
      (node (ref "C17") (pin "1") (pinfunction "1_1") (pintype "passive"))
      (node (ref "U4") (pin "3") (pinfunction "CAP1-_3") (pintype "passive"))
    )
    (net (code "58") (name "Net-(U4-CAP2+)") (class "Default")
      (node (ref "C16") (pin "2") (pinfunction "2_2") (pintype "passive"))
      (node (ref "U4") (pin "4") (pinfunction "CAP2+_4") (pintype "passive"))
    )
    (net (code "59") (name "Net-(U4-CAP2-)") (class "Default")
      (node (ref "C16") (pin "1") (pinfunction "1_1") (pintype "passive"))
      (node (ref "U4") (pin "5") (pinfunction "CAP2-_5") (pintype "passive"))
    )
    (net (code "60") (name "Net-(U5-CAP+)") (class "Default")
      (node (ref "C19") (pin "2") (pinfunction "2_2") (pintype "passive"))
      (node (ref "U5") (pin "2") (pinfunction "CAP+_2") (pintype "passive"))
    )
    (net (code "61") (name "Net-(U5-CAP-)") (class "Default")
      (node (ref "C18") (pin "2") (pinfunction "2_2") (pintype "passive"))
      (node (ref "U5") (pin "6") (pinfunction "CAP-_6") (pintype "passive"))
    )
    (net (code "62") (name "Net-(U5-CAP1+)") (class "Default")
      (node (ref "C21") (pin "2") (pinfunction "2_2") (pintype "passive"))
      (node (ref "U5") (pin "1") (pinfunction "CAP1+_1") (pintype "passive"))
    )
    (net (code "63") (name "Net-(U5-CAP1-)") (class "Default")
      (node (ref "C21") (pin "1") (pinfunction "1_1") (pintype "passive"))
      (node (ref "U5") (pin "3") (pinfunction "CAP1-_3") (pintype "passive"))
    )
    (net (code "64") (name "Net-(U5-CAP2+)") (class "Default")
      (node (ref "C20") (pin "2") (pinfunction "2_2") (pintype "passive"))
      (node (ref "U5") (pin "4") (pinfunction "CAP2+_4") (pintype "passive"))
    )
    (net (code "65") (name "Net-(U5-CAP2-)") (class "Default")
      (node (ref "C20") (pin "1") (pinfunction "1_1") (pintype "passive"))
      (node (ref "U5") (pin "5") (pinfunction "CAP2-_5") (pintype "passive"))
    )
    (net (code "66") (name "Net-(X1-OSC2)") (class "Default")
      (node (ref "R8") (pin "1") (pinfunction "1_1") (pintype "passive"))
      (node (ref "X1") (pin "3") (pinfunction "OSC2_3") (pintype "passive"))
    )
    (net (code "67") (name "unconnected-(P1-Pad13)") (class "Default")
      (node (ref "P1") (pin "13") (pinfunction "13_13") (pintype "passive"))
    )
    (net (code "68") (name "unconnected-(P1-Pad14)") (class "Default")
      (node (ref "P1") (pin "14") (pinfunction "14_14") (pintype "passive"))
    )
    (net (code "69") (name "unconnected-(P2-Pad4)") (class "Default")
      (node (ref "P2") (pin "4") (pinfunction "4_4") (pintype "passive"))
    )
    (net (code "70") (name "unconnected-(U1-EN-Pad2)") (class "Default")
      (node (ref "U1") (pin "2") (pinfunction "EN_2") (pintype "passive"))
    )
    (net (code "71") (name "unconnected-(U3A-NRST-Pad7)") (class "Default")
      (node (ref "U3") (pin "7") (pinfunction "NRST_7") (pintype "bidirectional"))
    )
    (net (code "72") (name "unconnected-(U3A-PA0-WKUP-Pad10)") (class "Default")
      (node (ref "U3") (pin "10") (pinfunction "PA0-WKUP_10") (pintype "bidirectional"))
    )
    (net (code "73") (name "unconnected-(U3A-PA1-Pad11)") (class "Default")
      (node (ref "U3") (pin "11") (pinfunction "PA1_11") (pintype "bidirectional"))
    )
    (net (code "74") (name "unconnected-(U3A-PA4-Pad14)") (class "Default")
      (node (ref "U3") (pin "14") (pinfunction "PA4_14") (pintype "bidirectional"))
    )
    (net (code "75") (name "unconnected-(U3A-PA5-Pad15)") (class "Default")
      (node (ref "U3") (pin "15") (pinfunction "PA5_15") (pintype "bidirectional"))
    )
    (net (code "76") (name "unconnected-(U3A-PA6-Pad16)") (class "Default")
      (node (ref "U3") (pin "16") (pinfunction "PA6_16") (pintype "bidirectional"))
    )
    (net (code "77") (name "unconnected-(U3A-PA7-Pad17)") (class "Default")
      (node (ref "U3") (pin "17") (pinfunction "PA7_17") (pintype "bidirectional"))
    )
    (net (code "78") (name "unconnected-(U3A-PA8-Pad29)") (class "Default")
      (node (ref "U3") (pin "29") (pinfunction "PA8_29") (pintype "bidirectional"))
    )
    (net (code "79") (name "unconnected-(U3A-PB0-Pad18)") (class "Default")
      (node (ref "U3") (pin "18") (pinfunction "PB0_18") (pintype "bidirectional"))
    )
    (net (code "80") (name "unconnected-(U3A-PB2-Pad20)") (class "Default")
      (node (ref "U3") (pin "20") (pinfunction "PB2_20") (pintype "bidirectional"))
    )
    (net (code "81") (name "unconnected-(U3A-PB5-Pad41)") (class "Default")
      (node (ref "U3") (pin "41") (pinfunction "PB5_41") (pintype "bidirectional"))
    )
    (net (code "82") (name "unconnected-(U3A-PB6-Pad42)") (class "Default")
      (node (ref "U3") (pin "42") (pinfunction "PB6_42") (pintype "bidirectional"))
    )
    (net (code "83") (name "unconnected-(U3A-PB7-Pad43)") (class "Default")
      (node (ref "U3") (pin "43") (pinfunction "PB7_43") (pintype "bidirectional"))
    )
    (net (code "84") (name "unconnected-(U3A-PB8-Pad45)") (class "Default")
      (node (ref "U3") (pin "45") (pinfunction "PB8_45") (pintype "bidirectional"))
    )
    (net (code "85") (name "unconnected-(U3A-PB9-Pad46)") (class "Default")
      (node (ref "U3") (pin "46") (pinfunction "PB9_46") (pintype "bidirectional"))
    )
    (net (code "86") (name "unconnected-(U3A-PB12-Pad25)") (class "Default")
      (node (ref "U3") (pin "25") (pinfunction "PB12_25") (pintype "bidirectional"))
    )
    (net (code "87") (name "unconnected-(U3A-PB14-Pad27)") (class "Default")
      (node (ref "U3") (pin "27") (pinfunction "PB14_27") (pintype "bidirectional"))
    )
    (net (code "88") (name "unconnected-(U3A-PB15-Pad28)") (class "Default")
      (node (ref "U3") (pin "28") (pinfunction "PB15_28") (pintype "bidirectional"))
    )
    (net (code "89") (name "unconnected-(U3A-PC13-TAMPER-RTC-Pad2)") (class "Default")
      (node (ref "U3") (pin "2") (pinfunction "PC13-TAMPER-RTC_2") (pintype "bidirectional"))
    )
    (net (code "90") (name "unconnected-(U3A-PC14-OSC32_IN-Pad3)") (class "Default")
      (node (ref "U3") (pin "3") (pinfunction "PC14-OSC32_IN_3") (pintype "bidirectional"))
    )
    (net (code "91") (name "unconnected-(U3A-PC15-OSC32_OUT-Pad4)") (class "Default")
      (node (ref "U3") (pin "4") (pinfunction "PC15-OSC32_OUT_4") (pintype "bidirectional"))
    )
    (net (code "92") (name "unconnected-(U5-R-OUT1-Pad12)") (class "Default")
      (node (ref "U5") (pin "12") (pinfunction "R-OUT1_12") (pintype "passive"))
    )
    (net (code "93") (name "unconnected-(U5-RR-IN1-Pad13)") (class "Default")
      (node (ref "U5") (pin "13") (pinfunction "RR-IN1_13") (pintype "passive"))
    )
    (net (code "94") (name "unconnected-(U5-RT-OUT1-Pad14)") (class "Default")
      (node (ref "U5") (pin "14") (pinfunction "RT-OUT1_14") (pintype "passive"))
    )
    (net (code "95") (name "unconnected-(U5-T-IN1-Pad11)") (class "Default")
      (node (ref "U5") (pin "11") (pinfunction "T-IN1_11") (pintype "passive"))
    )
  )
)
